# AK9750_Human_Movement_Sensor_Breakout.net
KiCad netlist of a schematic drawn in EAGLE
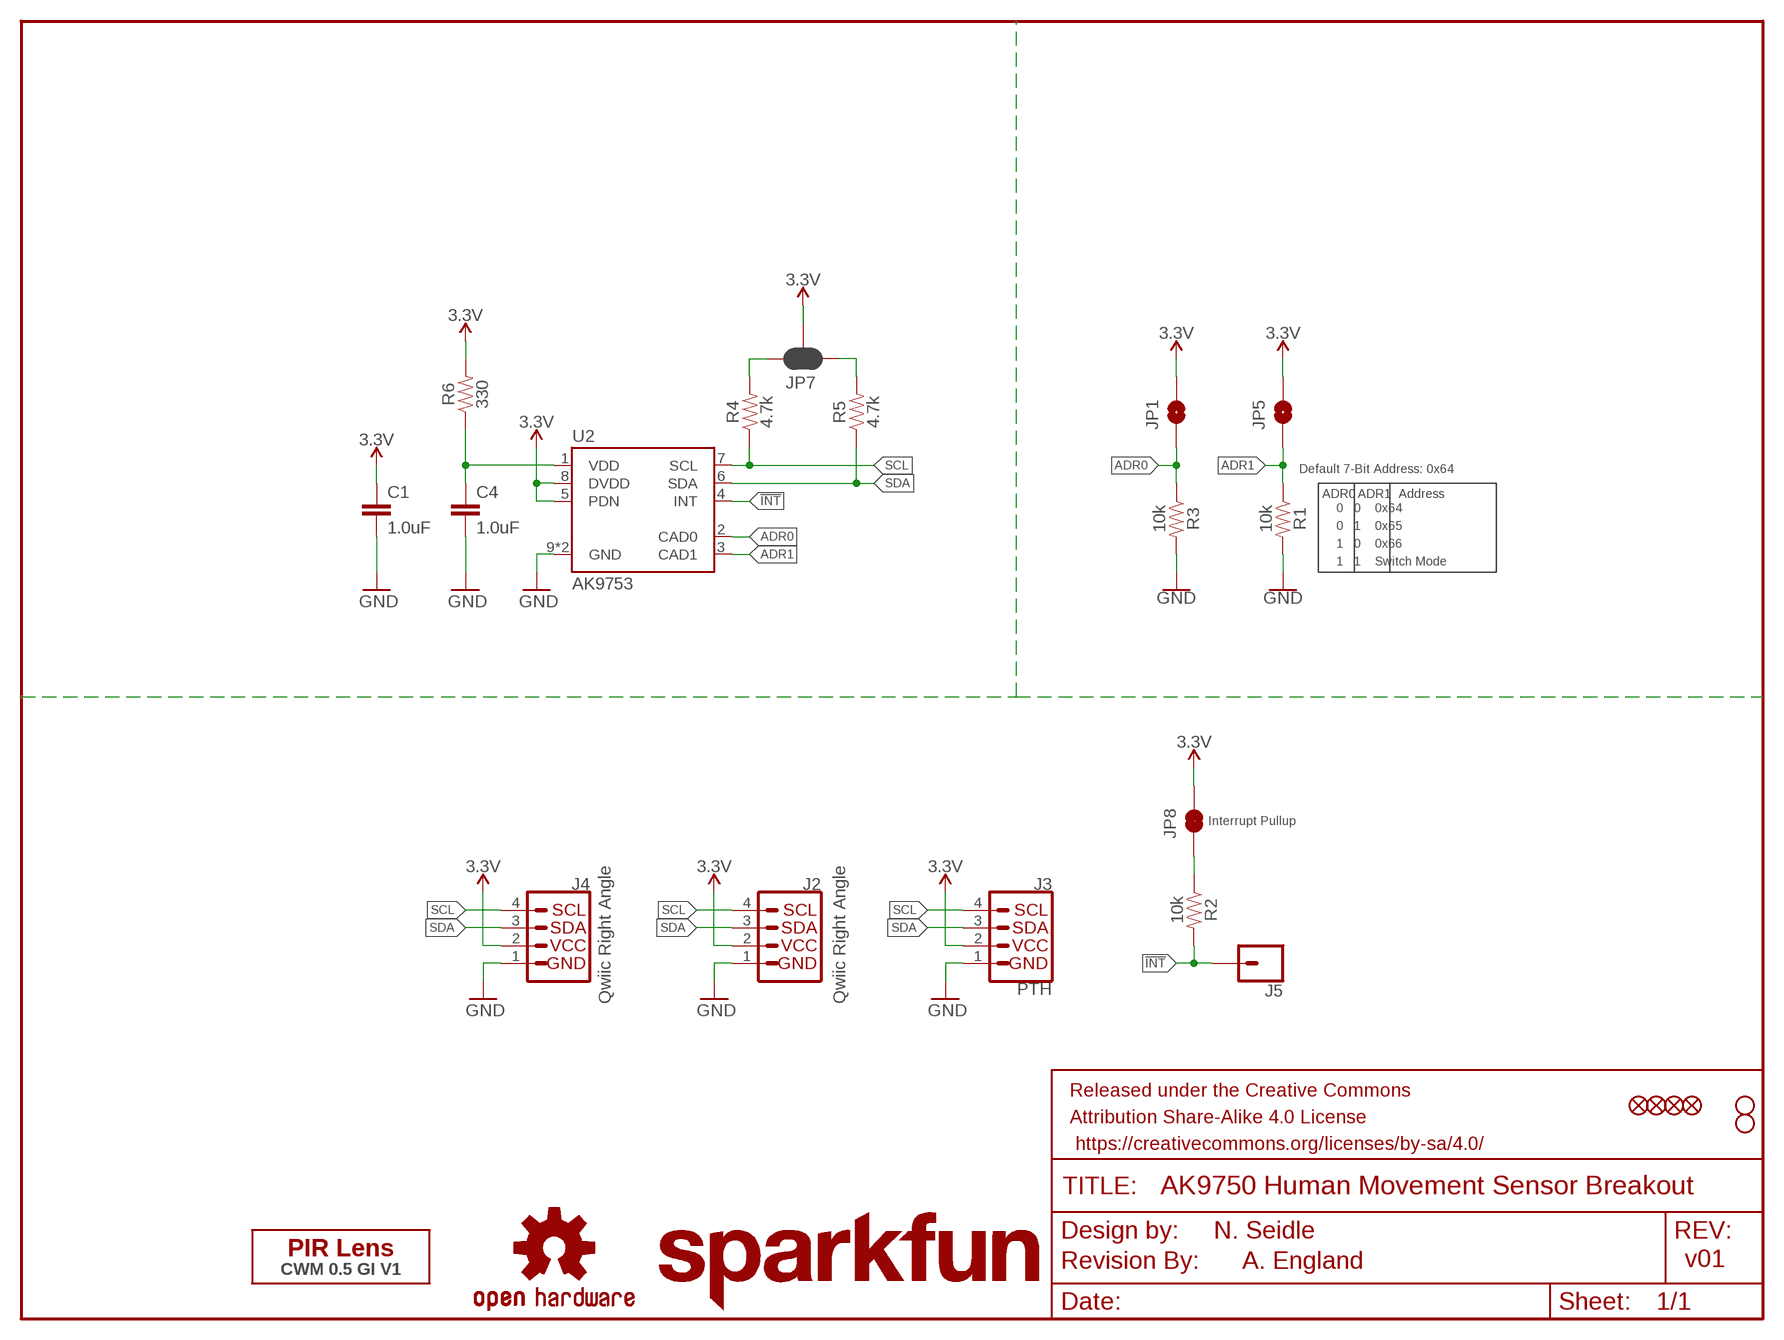
[diagram p0: schematic, sheet 1]

(export (version "E")
  (design (tool "Eeschema 10.0.6"))
  (components
    (comp (ref "C1")
      (value "1.0uF")
      (footprint "eagle-import:0603")
      (libsource (lib "eagle-import") (part "1.0UF-0603-16V-10%"))
    )
    (comp (ref "C4")
      (value "1.0uF")
      (footprint "eagle-import:0603")
      (libsource (lib "eagle-import") (part "1.0UF-0603-16V-10%"))
    )
    (comp (ref "FRAME1")
      (value "FRAME-LETTER")
      (footprint "eagle-import:CREATIVE_COMMONS")
      (libsource (lib "eagle-import") (part "FRAME-LETTER"))
    )
    (comp (ref "J2")
      (value "Qwiic Right Angle")
      (footprint "eagle-import:1X04_1MM_RA")
      (libsource (lib "eagle-import") (part "I2C_STANDARDQWIIC"))
    )
    (comp (ref "J3")
      (value "PTH")
      (footprint "eagle-import:1X04_NO_SILK")
      (libsource (lib "eagle-import") (part "I2C_STANDARD_NO_SILK"))
    )
    (comp (ref "J4")
      (value "Qwiic Right Angle")
      (footprint "eagle-import:1X04_1MM_RA")
      (libsource (lib "eagle-import") (part "I2C_STANDARDQWIIC"))
    )
    (comp (ref "J5")
      (value "CONN_01PTH_NO_SILK_YES_STOP")
      (footprint "eagle-import:1X01_NO_SILK")
      (libsource (lib "eagle-import") (part "CONN_01PTH_NO_SILK_YES_STOP"))
    )
    (comp (ref "JP1")
      (value "JUMPER-SMT_2_NO_SILK")
      (footprint "eagle-import:SMT-JUMPER_2_NO_SILK")
      (libsource (lib "eagle-import") (part "JUMPER-SMT_2_NO_SILK"))
    )
    (comp (ref "JP2")
      (value "FIDUCIALUFIDUCIAL")
      (footprint "eagle-import:MICRO-FIDUCIAL")
      (libsource (lib "eagle-import") (part "FIDUCIALUFIDUCIAL"))
    )
    (comp (ref "JP3")
      (value "STAND-OFF")
      (footprint "eagle-import:STAND-OFF")
      (libsource (lib "eagle-import") (part "STAND-OFF"))
    )
    (comp (ref "JP4")
      (value "STAND-OFF")
      (footprint "eagle-import:STAND-OFF")
      (libsource (lib "eagle-import") (part "STAND-OFF"))
    )
    (comp (ref "JP5")
      (value "JUMPER-SMT_2_NO_SILK")
      (footprint "eagle-import:SMT-JUMPER_2_NO_SILK")
      (libsource (lib "eagle-import") (part "JUMPER-SMT_2_NO_SILK"))
    )
    (comp (ref "JP6")
      (value "FIDUCIALUFIDUCIAL")
      (footprint "eagle-import:MICRO-FIDUCIAL")
      (libsource (lib "eagle-import") (part "FIDUCIALUFIDUCIAL"))
    )
    (comp (ref "JP7")
      (value "JUMPER-SMT_3_2-NC_PASTE_SILK")
      (footprint "eagle-import:SMT-JUMPER_3_2-NC_PASTE_SILK")
      (libsource (lib "eagle-import") (part "JUMPER-SMT_3_2-NC_PASTE_SILK"))
    )
    (comp (ref "JP8")
      (value "JUMPER-SMT_2_NC_TRACE_SILK")
      (footprint "eagle-import:SMT-JUMPER_2_NC_TRACE_SILK")
      (libsource (lib "eagle-import") (part "JUMPER-SMT_2_NC_TRACE_SILK"))
    )
    (comp (ref "JP9")
      (value "FIDUCIALUFIDUCIAL")
      (footprint "eagle-import:MICRO-FIDUCIAL")
      (libsource (lib "eagle-import") (part "FIDUCIALUFIDUCIAL"))
    )
    (comp (ref "JP10")
      (value "FIDUCIALUFIDUCIAL")
      (footprint "eagle-import:MICRO-FIDUCIAL")
      (libsource (lib "eagle-import") (part "FIDUCIALUFIDUCIAL"))
    )
    (comp (ref "LOGO1")
      (value "OSHW-LOGOMINI")
      (footprint "eagle-import:OSHW-LOGO-MINI")
      (libsource (lib "eagle-import") (part "OSHW-LOGOMINI"))
    )
    (comp (ref "LOGO2")
      (value "SFE_LOGO_NAME.1_INCH")
      (footprint "eagle-import:SFE_LOGO_NAME_.1")
      (libsource (lib "eagle-import") (part "SFE_LOGO_NAME.1_INCH"))
    )
    (comp (ref "LOGO3")
      (value "REVISION")
      (footprint "eagle-import:REVISION")
      (libsource (lib "eagle-import") (part "REVISION"))
    )
    (comp (ref "R1")
      (value "10k")
      (footprint "eagle-import:0603")
      (libsource (lib "eagle-import") (part "10KOHM-0603-1/10W-1%"))
    )
    (comp (ref "R2")
      (value "10k")
      (footprint "eagle-import:0603")
      (libsource (lib "eagle-import") (part "10KOHM-0603-1/10W-1%"))
    )
    (comp (ref "R3")
      (value "10k")
      (footprint "eagle-import:0603")
      (libsource (lib "eagle-import") (part "10KOHM-0603-1/10W-1%"))
    )
    (comp (ref "R4")
      (value "4.7k")
      (footprint "eagle-import:0603")
      (libsource (lib "eagle-import") (part "4.7KOHM-0603-1/10W-1%"))
    )
    (comp (ref "R5")
      (value "4.7k")
      (footprint "eagle-import:0603")
      (libsource (lib "eagle-import") (part "4.7KOHM-0603-1/10W-1%"))
    )
    (comp (ref "R6")
      (value "330")
      (footprint "eagle-import:0603")
      (libsource (lib "eagle-import") (part "330OHM-0603-1/10W-1%"))
    )
    (comp (ref "U$3")
      (value "CWM 0.5 GI V1")
      (footprint "eagle-import:LENS-CWM-0.5-GI-V1")
      (libsource (lib "eagle-import") (part "PIR-LENSCWM-0.5-GI-V1"))
    )
    (comp (ref "U2")
      (value "AK9753")
      (footprint "eagle-import:SON10")
      (libsource (lib "eagle-import") (part "AK9750{dblquote}"))
    )
  )
  (nets
    (net (code "1") (name "/~{INT}") (class "Default")
      (node (ref "J5") (pin "1") (pinfunction "1_1") (pintype "passive"))
      (node (ref "R2") (pin "2") (pinfunction "2_2") (pintype "passive"))
      (node (ref "U2") (pin "4") (pinfunction "INT_4") (pintype "bidirectional"))
    )
    (net (code "2") (name "3.3V") (class "Default")
      (node (ref "C1") (pin "1") (pinfunction "1_1") (pintype "passive"))
      (node (ref "J2") (pin "2") (pinfunction "2_2") (pintype "power_in"))
      (node (ref "J3") (pin "2") (pinfunction "2_2") (pintype "power_in"))
      (node (ref "J4") (pin "2") (pinfunction "2_2") (pintype "power_in"))
      (node (ref "JP1") (pin "2") (pinfunction "2_2") (pintype "passive"))
      (node (ref "JP5") (pin "2") (pinfunction "2_2") (pintype "passive"))
      (node (ref "JP7") (pin "2") (pinfunction "2_2") (pintype "passive"))
      (node (ref "JP8") (pin "2") (pinfunction "2_2") (pintype "passive"))
      (node (ref "R6") (pin "2") (pinfunction "2_2") (pintype "passive"))
      (node (ref "U2") (pin "5") (pinfunction "PDN_5") (pintype "bidirectional"))
      (node (ref "U2") (pin "8") (pinfunction "DVDD_8") (pintype "bidirectional"))
    )
    (net (code "3") (name "ADR0") (class "Default")
      (node (ref "JP1") (pin "1") (pinfunction "1_1") (pintype "passive"))
      (node (ref "R3") (pin "1") (pinfunction "1_1") (pintype "passive"))
      (node (ref "U2") (pin "2") (pinfunction "CAD0_2") (pintype "bidirectional"))
    )
    (net (code "4") (name "ADR1") (class "Default")
      (node (ref "JP5") (pin "1") (pinfunction "1_1") (pintype "passive"))
      (node (ref "R1") (pin "1") (pinfunction "1_1") (pintype "passive"))
      (node (ref "U2") (pin "3") (pinfunction "CAD1_3") (pintype "bidirectional"))
    )
    (net (code "5") (name "GND") (class "Default")
      (node (ref "C1") (pin "2") (pinfunction "2_2") (pintype "passive"))
      (node (ref "C4") (pin "2") (pinfunction "2_2") (pintype "passive"))
      (node (ref "J2") (pin "1") (pinfunction "1_1") (pintype "power_in"))
      (node (ref "J3") (pin "1") (pinfunction "1_1") (pintype "power_in"))
      (node (ref "J4") (pin "1") (pinfunction "1_1") (pintype "power_in"))
      (node (ref "R1") (pin "2") (pinfunction "2_2") (pintype "passive"))
      (node (ref "R3") (pin "2") (pinfunction "2_2") (pintype "passive"))
      (node (ref "U2") (pin "10") (pinfunction "GND_10") (pintype "bidirectional"))
      (node (ref "U2") (pin "9") (pinfunction "GND_9") (pintype "bidirectional"))
    )
    (net (code "6") (name "Net-(JP7-Pad1)") (class "Default")
      (node (ref "JP7") (pin "1") (pinfunction "1_1") (pintype "passive"))
      (node (ref "R5") (pin "2") (pinfunction "2_2") (pintype "passive"))
    )
    (net (code "7") (name "Net-(JP7-Pad3)") (class "Default")
      (node (ref "JP7") (pin "3") (pinfunction "3_3") (pintype "passive"))
      (node (ref "R4") (pin "2") (pinfunction "2_2") (pintype "passive"))
    )
    (net (code "8") (name "Net-(JP8-Pad1)") (class "Default")
      (node (ref "JP8") (pin "1") (pinfunction "1_1") (pintype "passive"))
      (node (ref "R2") (pin "1") (pinfunction "1_1") (pintype "passive"))
    )
    (net (code "9") (name "Net-(U2-VDD)") (class "Default")
      (node (ref "C4") (pin "1") (pinfunction "1_1") (pintype "passive"))
      (node (ref "R6") (pin "1") (pinfunction "1_1") (pintype "passive"))
      (node (ref "U2") (pin "1") (pinfunction "VDD_1") (pintype "bidirectional"))
    )
    (net (code "10") (name "SCL") (class "Default")
      (node (ref "J2") (pin "4") (pinfunction "4_4") (pintype "passive"))
      (node (ref "J3") (pin "4") (pinfunction "4_4") (pintype "passive"))
      (node (ref "J4") (pin "4") (pinfunction "4_4") (pintype "passive"))
      (node (ref "R4") (pin "1") (pinfunction "1_1") (pintype "passive"))
      (node (ref "U2") (pin "7") (pinfunction "SCL_7") (pintype "bidirectional"))
    )
    (net (code "11") (name "SDA") (class "Default")
      (node (ref "J2") (pin "3") (pinfunction "3_3") (pintype "passive"))
      (node (ref "J3") (pin "3") (pinfunction "3_3") (pintype "passive"))
      (node (ref "J4") (pin "3") (pinfunction "3_3") (pintype "passive"))
      (node (ref "R5") (pin "1") (pinfunction "1_1") (pintype "passive"))
      (node (ref "U2") (pin "6") (pinfunction "SDA_6") (pintype "bidirectional"))
    )
  )
)
